# Esquematico_V2b.net
KiCad netlist of a schematic drawn in Altium Designer
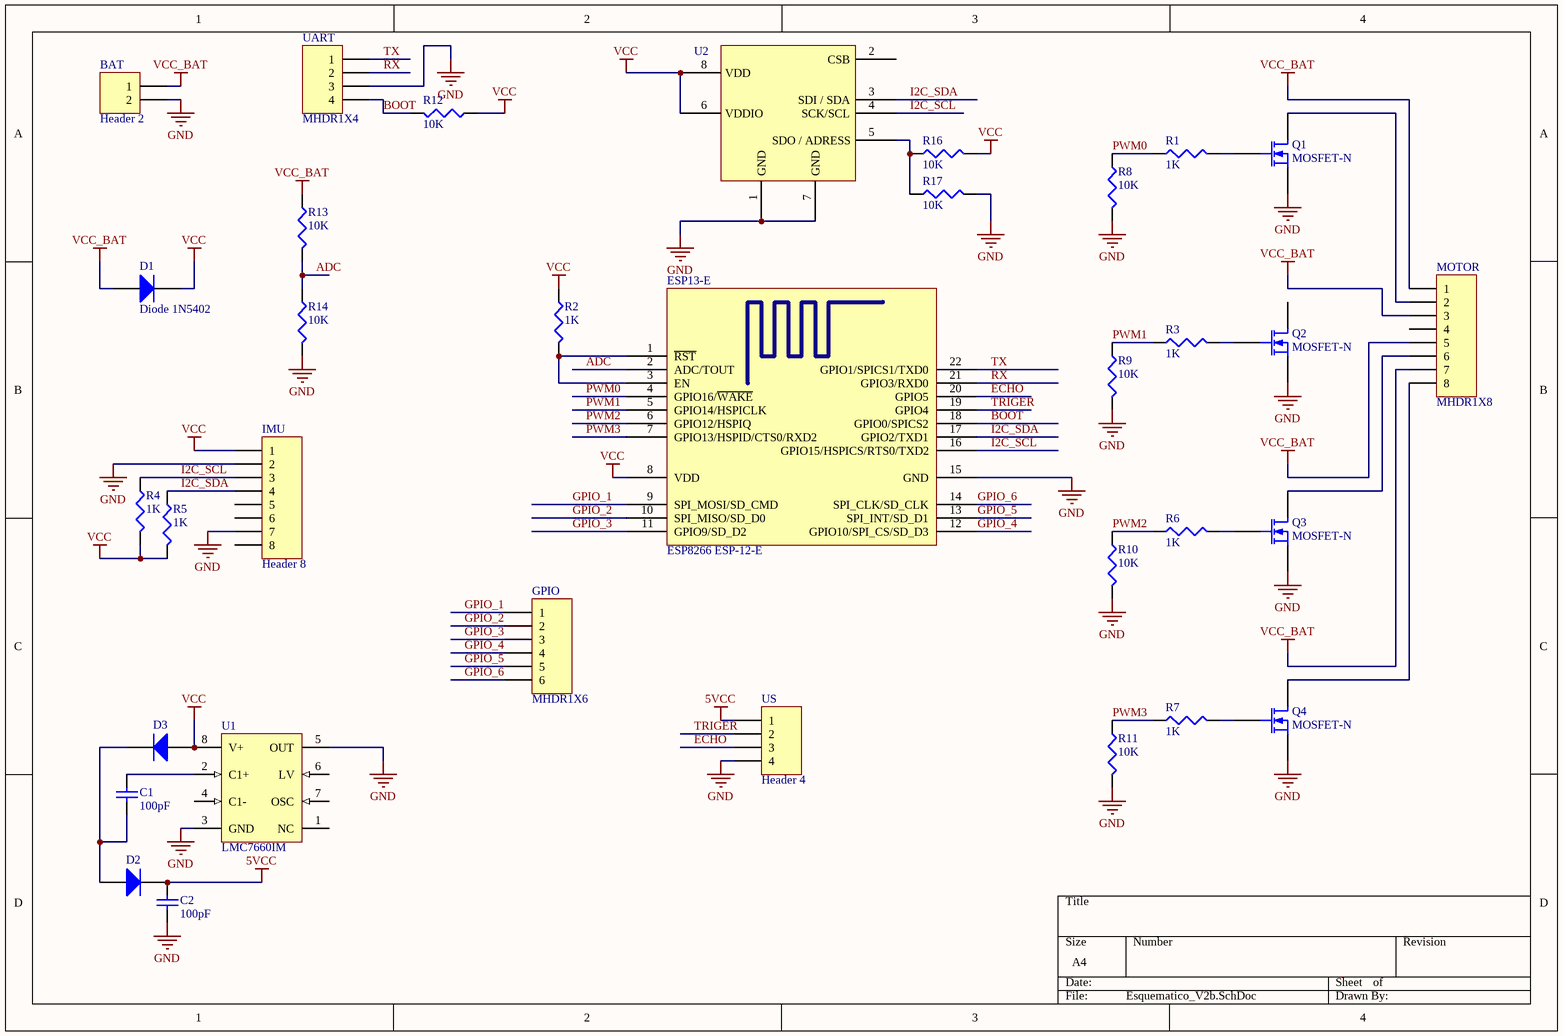
[diagram p0: Esquematico_V2b.SchDoc]

(export (version "E")
  (design (tool "Eeschema 10.0.6"))
  (components
    (comp (ref "BAT")
      (value "Header 2")
      (footprint "Miscellaneous Connectors:MHDR1X2")
      (description "Header, 2-Pin")
      (fields (field (name "PUBLISHER") "Altium Limited"))
      (libsource (lib "Miscellaneous Connectors") (part "Header 2"))
    )
    (comp (ref "C1")
      (value "100pF")
      (footprint "Miscellaneous Devices:C0805")
      (description "Capacitor")
      (fields (field (name "Comment") "Cap") (field (name "PUBLISHER") "Altium Limited"))
      (libsource (lib "Miscellaneous Devices") (part "Cap"))
    )
    (comp (ref "C2")
      (value "100pF")
      (footprint "Miscellaneous Devices:C0805")
      (description "Capacitor")
      (fields (field (name "Comment") "Cap") (field (name "PUBLISHER") "Altium Limited"))
      (libsource (lib "Miscellaneous Devices") (part "Cap"))
    )
    (comp (ref "D1")
      (value "Diode 1N5402")
      (footprint "DSO-C2/X2.3")
      (description "3 Amp General Purpose Rectifier")
      (fields (field (name "PUBLISHER") "Altium Limited"))
      (libsource (lib "Miscellaneous Devices") (part "Diode 1N5402"))
    )
    (comp (ref "D2")
      (value "Diode 1N5402")
      (footprint "DSO-C2/Z6.7")
      (description "3 Amp General Purpose Rectifier")
      (fields (field (name "PUBLISHER") "Altium Limited"))
      (libsource (lib "Miscellaneous Devices") (part "Diode 1N5402"))
    )
    (comp (ref "D3")
      (value "Diode 1N5402")
      (footprint "DSO-C2/Z6.7")
      (description "3 Amp General Purpose Rectifier")
      (fields (field (name "PUBLISHER") "Altium Limited"))
      (libsource (lib "Miscellaneous Devices") (part "Diode 1N5402"))
    )
    (comp (ref "ESP13-E")
      (value "ESP8266 ESP-12-E")
      (footprint "ESP8266:ESP8266 ESP-12-E B")
      (libsource (lib "ESP8266") (part "ESP8266 ESP-12-E"))
    )
    (comp (ref "GPIO")
      (value "MHDR1X6")
      (footprint "MHDR1X6")
      (description "Header, 6-Pin")
      (fields (field (name "PUBLISHER") "Altium Limited"))
      (libsource (lib "Miscellaneous Connectors") (part "MHDR1X6"))
    )
    (comp (ref "IMU")
      (value "Header 8")
      (footprint "HDR1X8")
      (description "Header, 8-Pin")
      (fields (field (name "PUBLISHER") "Altium Limited"))
      (libsource (lib "Miscellaneous Connectors") (part "Header 8"))
    )
    (comp (ref "MOTOR")
      (value "MHDR1X8")
      (footprint "MHDR1X8")
      (description "Header, 8-Pin")
      (fields (field (name "PUBLISHER") "Altium Limited"))
      (libsource (lib "Miscellaneous Connectors") (part "MHDR1X8"))
    )
    (comp (ref "Q1")
      (value "MOSFET-N")
      (footprint "PBL - SMD Packages:SOT23-3")
      (description "N-Channel MOSFET")
      (fields (field (name "PUBLISHER") "Altium Limited"))
      (libsource (lib "Miscellaneous Devices") (part "MOSFET-N"))
    )
    (comp (ref "Q2")
      (value "MOSFET-N")
      (footprint "PBL - SMD Packages:SOT23-3")
      (description "N-Channel MOSFET")
      (fields (field (name "PUBLISHER") "Altium Limited"))
      (libsource (lib "Miscellaneous Devices") (part "MOSFET-N"))
    )
    (comp (ref "Q3")
      (value "MOSFET-N")
      (footprint "PBL - SMD Packages:SOT23-3")
      (description "N-Channel MOSFET")
      (fields (field (name "PUBLISHER") "Altium Limited"))
      (libsource (lib "Miscellaneous Devices") (part "MOSFET-N"))
    )
    (comp (ref "Q4")
      (value "MOSFET-N")
      (footprint "PBL - SMD Packages:SOT23-3")
      (description "N-Channel MOSFET")
      (fields (field (name "PUBLISHER") "Altium Limited"))
      (libsource (lib "Miscellaneous Devices") (part "MOSFET-N"))
    )
    (comp (ref "R1")
      (value "1K")
      (footprint "C0805")
      (description "Resistor")
      (fields (field (name "Comment") "Res3") (field (name "PUBLISHER") "Altium Limited"))
      (libsource (lib "Miscellaneous Devices") (part "Res3"))
    )
    (comp (ref "R2")
      (value "1K")
      (footprint "C0805")
      (description "Resistor")
      (fields (field (name "Comment") "Res3") (field (name "PUBLISHER") "Altium Limited"))
      (libsource (lib "Miscellaneous Devices") (part "Res3"))
    )
    (comp (ref "R3")
      (value "1K")
      (footprint "C0805")
      (description "Resistor")
      (fields (field (name "Comment") "Res3") (field (name "PUBLISHER") "Altium Limited"))
      (libsource (lib "Miscellaneous Devices") (part "Res3"))
    )
    (comp (ref "R4")
      (value "1K")
      (footprint "C1206")
      (description "Resistor")
      (fields (field (name "Comment") "Res3") (field (name "PUBLISHER") "Altium Limited"))
      (libsource (lib "Miscellaneous Devices") (part "Res3"))
    )
    (comp (ref "R5")
      (value "1K")
      (footprint "C1206")
      (description "Resistor")
      (fields (field (name "Comment") "Res3") (field (name "PUBLISHER") "Altium Limited"))
      (libsource (lib "Miscellaneous Devices") (part "Res3"))
    )
    (comp (ref "R6")
      (value "1K")
      (footprint "C0805")
      (description "Resistor")
      (fields (field (name "Comment") "Res3") (field (name "PUBLISHER") "Altium Limited"))
      (libsource (lib "Miscellaneous Devices") (part "Res3"))
    )
    (comp (ref "R7")
      (value "1K")
      (footprint "C0805")
      (description "Resistor")
      (fields (field (name "Comment") "Res3") (field (name "PUBLISHER") "Altium Limited"))
      (libsource (lib "Miscellaneous Devices") (part "Res3"))
    )
    (comp (ref "R8")
      (value "10K")
      (footprint "C0805")
      (description "Resistor")
      (fields (field (name "Comment") "Res3") (field (name "PUBLISHER") "Altium Limited"))
      (libsource (lib "Miscellaneous Devices") (part "Res3"))
    )
    (comp (ref "R9")
      (value "10K")
      (footprint "C0805")
      (description "Resistor")
      (fields (field (name "Comment") "Res3") (field (name "PUBLISHER") "Altium Limited"))
      (libsource (lib "Miscellaneous Devices") (part "Res3"))
    )
    (comp (ref "R10")
      (value "10K")
      (footprint "C0805")
      (description "Resistor")
      (fields (field (name "Comment") "Res3") (field (name "PUBLISHER") "Altium Limited"))
      (libsource (lib "Miscellaneous Devices") (part "Res3"))
    )
    (comp (ref "R11")
      (value "10K")
      (footprint "C0805")
      (description "Resistor")
      (fields (field (name "Comment") "Res3") (field (name "PUBLISHER") "Altium Limited"))
      (libsource (lib "Miscellaneous Devices") (part "Res3"))
    )
    (comp (ref "R12")
      (value "10K")
      (footprint "C1206")
      (description "Resistor")
      (fields (field (name "Comment") "Res3") (field (name "PUBLISHER") "Altium Limited"))
      (libsource (lib "Miscellaneous Devices") (part "Res3"))
    )
    (comp (ref "R13")
      (value "10K")
      (footprint "C0805")
      (description "Resistor")
      (fields (field (name "Comment") "Res3") (field (name "PUBLISHER") "Altium Limited"))
      (libsource (lib "Miscellaneous Devices") (part "Res3"))
    )
    (comp (ref "R14")
      (value "10K")
      (footprint "C0805")
      (description "Resistor")
      (fields (field (name "Comment") "Res3") (field (name "PUBLISHER") "Altium Limited"))
      (libsource (lib "Miscellaneous Devices") (part "Res3"))
    )
    (comp (ref "R16")
      (value "10K")
      (footprint "C0805")
      (description "Resistor")
      (fields (field (name "Comment") "Res3") (field (name "PUBLISHER") "Altium Limited"))
      (libsource (lib "Miscellaneous Devices") (part "Res3"))
    )
    (comp (ref "R17")
      (value "10K")
      (footprint "C0805")
      (description "Resistor")
      (fields (field (name "Comment") "Res3") (field (name "PUBLISHER") "Altium Limited"))
      (libsource (lib "Miscellaneous Devices") (part "Res3"))
    )
    (comp (ref "U1")
      (value "LMC7660IM")
      (footprint "M08A_N")
      (description "Switched Capacitor Voltage Converter, 8-pin Narrow SOIC")
      (fields
        (field (name "MANUFACTURER") "National Semiconductor")
        (field (name "PUBLISHER") "Altium Limited")
      )
      (libsource (lib "NSC Switch Caps") (part "LMC7660IM"))
    )
    (comp (ref "U2")
      (value "BMP280")
      (footprint "LGA-8_BMP280(Primary)")
      (description "Barometro")
      (libsource (lib "BMP280") (part "BMP280"))
    )
    (comp (ref "UART")
      (value "MHDR1X4")
      (footprint "MHDR1X4")
      (description "Header, 4-Pin")
      (fields (field (name "PUBLISHER") "Altium Limited"))
      (libsource (lib "Miscellaneous Connectors") (part "MHDR1X4"))
    )
    (comp (ref "US")
      (value "Header 4")
      (footprint "HDR1X4")
      (description "Header, 4-Pin")
      (fields (field (name "PUBLISHER") "Altium Limited"))
      (libsource (lib "Miscellaneous Connectors") (part "Header 4"))
    )
  )
  (nets
    (net (code "1") (name "/ADC") (class "Default")
      (node (ref "ESP13-E") (pin "2") (pinfunction "ADC/TOUT_2") (pintype "passive"))
      (node (ref "R13") (pin "2") (pinfunction "2_2") (pintype "passive"))
      (node (ref "R14") (pin "1") (pinfunction "1_1") (pintype "passive"))
    )
    (net (code "2") (name "/BOOT") (class "Default")
      (node (ref "ESP13-E") (pin "18") (pinfunction "GPIO0/SPICS2_18") (pintype "passive"))
      (node (ref "R12") (pin "2") (pinfunction "2_2") (pintype "passive"))
      (node (ref "UART") (pin "4") (pinfunction "4_4") (pintype "passive"))
    )
    (net (code "3") (name "/ECHO") (class "Default")
      (node (ref "ESP13-E") (pin "20") (pinfunction "GPIO5_20") (pintype "passive"))
      (node (ref "US") (pin "3") (pinfunction "3_3") (pintype "passive"))
    )
    (net (code "4") (name "/GPIO_1") (class "Default")
      (node (ref "ESP13-E") (pin "9") (pinfunction "SPI_MOSI/SD_CMD_9") (pintype "passive"))
      (node (ref "GPIO") (pin "1") (pinfunction "1_1") (pintype "passive"))
    )
    (net (code "5") (name "/GPIO_2") (class "Default")
      (node (ref "ESP13-E") (pin "10") (pinfunction "SPI_MISO/SD_D0_10") (pintype "passive"))
      (node (ref "GPIO") (pin "2") (pinfunction "2_2") (pintype "passive"))
    )
    (net (code "6") (name "/GPIO_3") (class "Default")
      (node (ref "ESP13-E") (pin "11") (pinfunction "GPIO9/SD_D2_11") (pintype "passive"))
      (node (ref "GPIO") (pin "3") (pinfunction "3_3") (pintype "passive"))
    )
    (net (code "7") (name "/GPIO_4") (class "Default")
      (node (ref "ESP13-E") (pin "12") (pinfunction "GPIO10/SPI_CS/SD_D3_12") (pintype "passive"))
      (node (ref "GPIO") (pin "4") (pinfunction "4_4") (pintype "passive"))
    )
    (net (code "8") (name "/GPIO_5") (class "Default")
      (node (ref "ESP13-E") (pin "13") (pinfunction "SPI_INT/SD_D1_13") (pintype "passive"))
      (node (ref "GPIO") (pin "5") (pinfunction "5_5") (pintype "passive"))
    )
    (net (code "9") (name "/GPIO_6") (class "Default")
      (node (ref "ESP13-E") (pin "14") (pinfunction "SPI_CLK/SD_CLK_14") (pintype "passive"))
      (node (ref "GPIO") (pin "6") (pinfunction "6_6") (pintype "passive"))
    )
    (net (code "10") (name "/I2C_SCL") (class "Default")
      (node (ref "ESP13-E") (pin "16") (pinfunction "GPIO15/HSPICS/RTS0/TXD2_16") (pintype "passive"))
      (node (ref "IMU") (pin "3") (pinfunction "3_3") (pintype "passive"))
      (node (ref "R4") (pin "1") (pinfunction "1_1") (pintype "passive"))
      (node (ref "U2") (pin "4") (pinfunction "SCK/SCL_4") (pintype "passive"))
    )
    (net (code "11") (name "/I2C_SDA") (class "Default")
      (node (ref "ESP13-E") (pin "17") (pinfunction "GPIO2/TXD1_17") (pintype "passive"))
      (node (ref "IMU") (pin "4") (pinfunction "4_4") (pintype "passive"))
      (node (ref "R5") (pin "1") (pinfunction "1_1") (pintype "passive"))
      (node (ref "U2") (pin "3") (pinfunction "SDI_/_SDA_3") (pintype "passive"))
    )
    (net (code "12") (name "/PWM0") (class "Default")
      (node (ref "ESP13-E") (pin "4") (pinfunction "GPIO16/~{WAKE}_4") (pintype "passive"))
      (node (ref "R1") (pin "1") (pinfunction "1_1") (pintype "passive"))
      (node (ref "R8") (pin "1") (pinfunction "1_1") (pintype "passive"))
    )
    (net (code "13") (name "/PWM1") (class "Default")
      (node (ref "ESP13-E") (pin "5") (pinfunction "GPIO14/HSPICLK_5") (pintype "passive"))
      (node (ref "R3") (pin "1") (pinfunction "1_1") (pintype "passive"))
      (node (ref "R9") (pin "1") (pinfunction "1_1") (pintype "passive"))
    )
    (net (code "14") (name "/PWM2") (class "Default")
      (node (ref "ESP13-E") (pin "6") (pinfunction "GPIO12/HSPIQ_6") (pintype "passive"))
      (node (ref "R10") (pin "1") (pinfunction "1_1") (pintype "passive"))
      (node (ref "R6") (pin "1") (pinfunction "1_1") (pintype "passive"))
    )
    (net (code "15") (name "/PWM3") (class "Default")
      (node (ref "ESP13-E") (pin "7") (pinfunction "GPIO13/HSPID/CTS0/RXD2_7") (pintype "passive"))
      (node (ref "R11") (pin "1") (pinfunction "1_1") (pintype "passive"))
      (node (ref "R7") (pin "1") (pinfunction "1_1") (pintype "passive"))
    )
    (net (code "16") (name "/RX") (class "Default")
      (node (ref "ESP13-E") (pin "21") (pinfunction "GPIO3/RXD0_21") (pintype "passive"))
      (node (ref "UART") (pin "2") (pinfunction "2_2") (pintype "passive"))
    )
    (net (code "17") (name "/TRIGER") (class "Default")
      (node (ref "ESP13-E") (pin "19") (pinfunction "GPIO4_19") (pintype "passive"))
      (node (ref "US") (pin "2") (pinfunction "2_2") (pintype "passive"))
    )
    (net (code "18") (name "/TX") (class "Default")
      (node (ref "ESP13-E") (pin "22") (pinfunction "GPIO1/SPICS1/TXD0_22") (pintype "passive"))
      (node (ref "UART") (pin "1") (pinfunction "1_1") (pintype "passive"))
    )
    (net (code "19") (name "5VCC") (class "Default")
      (node (ref "C2") (pin "2") (pinfunction "2_2") (pintype "passive"))
      (node (ref "D2") (pin "2") (pinfunction "K_2") (pintype "passive"))
      (node (ref "US") (pin "1") (pinfunction "1_1") (pintype "passive"))
    )
    (net (code "20") (name "GND") (class "Default")
      (node (ref "BAT") (pin "2") (pinfunction "2_2") (pintype "passive"))
      (node (ref "C2") (pin "1") (pinfunction "1_1") (pintype "passive"))
      (node (ref "ESP13-E") (pin "15") (pinfunction "GND_15") (pintype "passive"))
      (node (ref "IMU") (pin "2") (pinfunction "2_2") (pintype "passive"))
      (node (ref "IMU") (pin "7") (pinfunction "7_7") (pintype "passive"))
      (node (ref "Q1") (pin "3") (pinfunction "S_3") (pintype "passive"))
      (node (ref "Q2") (pin "3") (pinfunction "S_3") (pintype "passive"))
      (node (ref "Q3") (pin "3") (pinfunction "S_3") (pintype "passive"))
      (node (ref "Q4") (pin "3") (pinfunction "S_3") (pintype "passive"))
      (node (ref "R10") (pin "2") (pinfunction "2_2") (pintype "passive"))
      (node (ref "R11") (pin "2") (pinfunction "2_2") (pintype "passive"))
      (node (ref "R14") (pin "2") (pinfunction "2_2") (pintype "passive"))
      (node (ref "R17") (pin "2") (pinfunction "2_2") (pintype "passive"))
      (node (ref "R8") (pin "2") (pinfunction "2_2") (pintype "passive"))
      (node (ref "R9") (pin "2") (pinfunction "2_2") (pintype "passive"))
      (node (ref "U1") (pin "3") (pinfunction "GND_3") (pintype "power_in"))
      (node (ref "U1") (pin "5") (pinfunction "OUT_5") (pintype "power_in"))
      (node (ref "U2") (pin "1") (pinfunction "GND_1") (pintype "passive"))
      (node (ref "U2") (pin "7") (pinfunction "GND_7") (pintype "passive"))
      (node (ref "UART") (pin "3") (pinfunction "3_3") (pintype "passive"))
      (node (ref "US") (pin "4") (pinfunction "4_4") (pintype "passive"))
    )
    (net (code "21") (name "Net-(D2-A)") (class "Default")
      (node (ref "C1") (pin "2") (pinfunction "2_2") (pintype "passive"))
      (node (ref "D2") (pin "1") (pinfunction "A_1") (pintype "passive"))
      (node (ref "D3") (pin "2") (pinfunction "K_2") (pintype "passive"))
    )
    (net (code "22") (name "Net-(ESP13-E-EN)") (class "Default")
      (node (ref "ESP13-E") (pin "1") (pinfunction "~{RST}_1") (pintype "passive"))
      (node (ref "ESP13-E") (pin "3") (pinfunction "EN_3") (pintype "passive"))
      (node (ref "R2") (pin "2") (pinfunction "2_2") (pintype "passive"))
    )
    (net (code "23") (name "Net-(Q1-D)") (class "Default")
      (node (ref "MOTOR") (pin "2") (pinfunction "2_2") (pintype "passive"))
      (node (ref "Q1") (pin "1") (pinfunction "D_1") (pintype "passive"))
    )
    (net (code "24") (name "Net-(Q1-G)") (class "Default")
      (node (ref "Q1") (pin "2") (pinfunction "G_2") (pintype "passive"))
      (node (ref "R1") (pin "2") (pinfunction "2_2") (pintype "passive"))
    )
    (net (code "25") (name "Net-(Q2-G)") (class "Default")
      (node (ref "Q2") (pin "2") (pinfunction "G_2") (pintype "passive"))
      (node (ref "R3") (pin "2") (pinfunction "2_2") (pintype "passive"))
    )
    (net (code "26") (name "Net-(Q3-D)") (class "Default")
      (node (ref "MOTOR") (pin "6") (pinfunction "6_6") (pintype "passive"))
      (node (ref "Q3") (pin "1") (pinfunction "D_1") (pintype "passive"))
    )
    (net (code "27") (name "Net-(Q3-G)") (class "Default")
      (node (ref "Q3") (pin "2") (pinfunction "G_2") (pintype "passive"))
      (node (ref "R6") (pin "2") (pinfunction "2_2") (pintype "passive"))
    )
    (net (code "28") (name "Net-(Q4-D)") (class "Default")
      (node (ref "MOTOR") (pin "8") (pinfunction "8_8") (pintype "passive"))
      (node (ref "Q4") (pin "1") (pinfunction "D_1") (pintype "passive"))
    )
    (net (code "29") (name "Net-(Q4-G)") (class "Default")
      (node (ref "Q4") (pin "2") (pinfunction "G_2") (pintype "passive"))
      (node (ref "R7") (pin "2") (pinfunction "2_2") (pintype "passive"))
    )
    (net (code "30") (name "Net-(U1-C1+)") (class "Default")
      (node (ref "C1") (pin "1") (pinfunction "1_1") (pintype "passive"))
      (node (ref "U1") (pin "2") (pinfunction "C1+_2") (pintype "input"))
    )
    (net (code "31") (name "Net-(U2-SDO_{slash}_ADRESS)") (class "Default")
      (node (ref "R16") (pin "1") (pinfunction "1_1") (pintype "passive"))
      (node (ref "R17") (pin "1") (pinfunction "1_1") (pintype "passive"))
      (node (ref "U2") (pin "5") (pinfunction "SDO_/_ADRESS_5") (pintype "passive"))
    )
    (net (code "32") (name "VCC") (class "Default")
      (node (ref "D1") (pin "2") (pinfunction "K_2") (pintype "passive"))
      (node (ref "D3") (pin "1") (pinfunction "A_1") (pintype "passive"))
      (node (ref "ESP13-E") (pin "8") (pinfunction "VDD_8") (pintype "passive"))
      (node (ref "IMU") (pin "1") (pinfunction "1_1") (pintype "passive"))
      (node (ref "R12") (pin "1") (pinfunction "1_1") (pintype "passive"))
      (node (ref "R16") (pin "2") (pinfunction "2_2") (pintype "passive"))
      (node (ref "R2") (pin "1") (pinfunction "1_1") (pintype "passive"))
      (node (ref "R4") (pin "2") (pinfunction "2_2") (pintype "passive"))
      (node (ref "R5") (pin "2") (pinfunction "2_2") (pintype "passive"))
      (node (ref "U1") (pin "8") (pinfunction "V+_8") (pintype "power_in"))
      (node (ref "U2") (pin "6") (pinfunction "VDDIO_6") (pintype "passive"))
      (node (ref "U2") (pin "8") (pinfunction "VDD_8") (pintype "passive"))
    )
    (net (code "33") (name "VCC_BAT") (class "Default")
      (node (ref "BAT") (pin "1") (pinfunction "1_1") (pintype "passive"))
      (node (ref "D1") (pin "1") (pinfunction "A_1") (pintype "passive"))
      (node (ref "MOTOR") (pin "1") (pinfunction "1_1") (pintype "passive"))
      (node (ref "MOTOR") (pin "3") (pinfunction "3_3") (pintype "passive"))
      (node (ref "MOTOR") (pin "5") (pinfunction "5_5") (pintype "passive"))
      (node (ref "MOTOR") (pin "7") (pinfunction "7_7") (pintype "passive"))
      (node (ref "R13") (pin "1") (pinfunction "1_1") (pintype "passive"))
    )
    (net (code "34") (name "unconnected-(IMU-Pad5)") (class "Default")
      (node (ref "IMU") (pin "5") (pinfunction "5_5") (pintype "passive"))
    )
    (net (code "35") (name "unconnected-(IMU-Pad6)") (class "Default")
      (node (ref "IMU") (pin "6") (pinfunction "6_6") (pintype "passive"))
    )
    (net (code "36") (name "unconnected-(IMU-Pad8)") (class "Default")
      (node (ref "IMU") (pin "8") (pinfunction "8_8") (pintype "passive"))
    )
    (net (code "37") (name "unconnected-(MOTOR-Pad4)") (class "Default")
      (node (ref "MOTOR") (pin "4") (pinfunction "4_4") (pintype "passive"))
    )
    (net (code "38") (name "unconnected-(Q2-D-Pad1)") (class "Default")
      (node (ref "Q2") (pin "1") (pinfunction "D_1") (pintype "passive"))
    )
    (net (code "39") (name "unconnected-(U1-C1--Pad4)") (class "Default")
      (node (ref "U1") (pin "4") (pinfunction "C1-_4") (pintype "input"))
    )
    (net (code "40") (name "unconnected-(U1-LV-Pad6)") (class "Default")
      (node (ref "U1") (pin "6") (pinfunction "LV_6") (pintype "input"))
    )
    (net (code "41") (name "unconnected-(U1-NC-Pad1)") (class "Default")
      (node (ref "U1") (pin "1") (pinfunction "NC_1") (pintype "passive"))
    )
    (net (code "42") (name "unconnected-(U1-OSC-Pad7)") (class "Default")
      (node (ref "U1") (pin "7") (pinfunction "OSC_7") (pintype "input"))
    )
    (net (code "43") (name "unconnected-(U2-CSB-Pad2)") (class "Default")
      (node (ref "U2") (pin "2") (pinfunction "CSB_2") (pintype "passive"))
    )
  )
)
